# aspirin_carrier_board.net
KiCad netlist of a schematic drawn in EAGLE
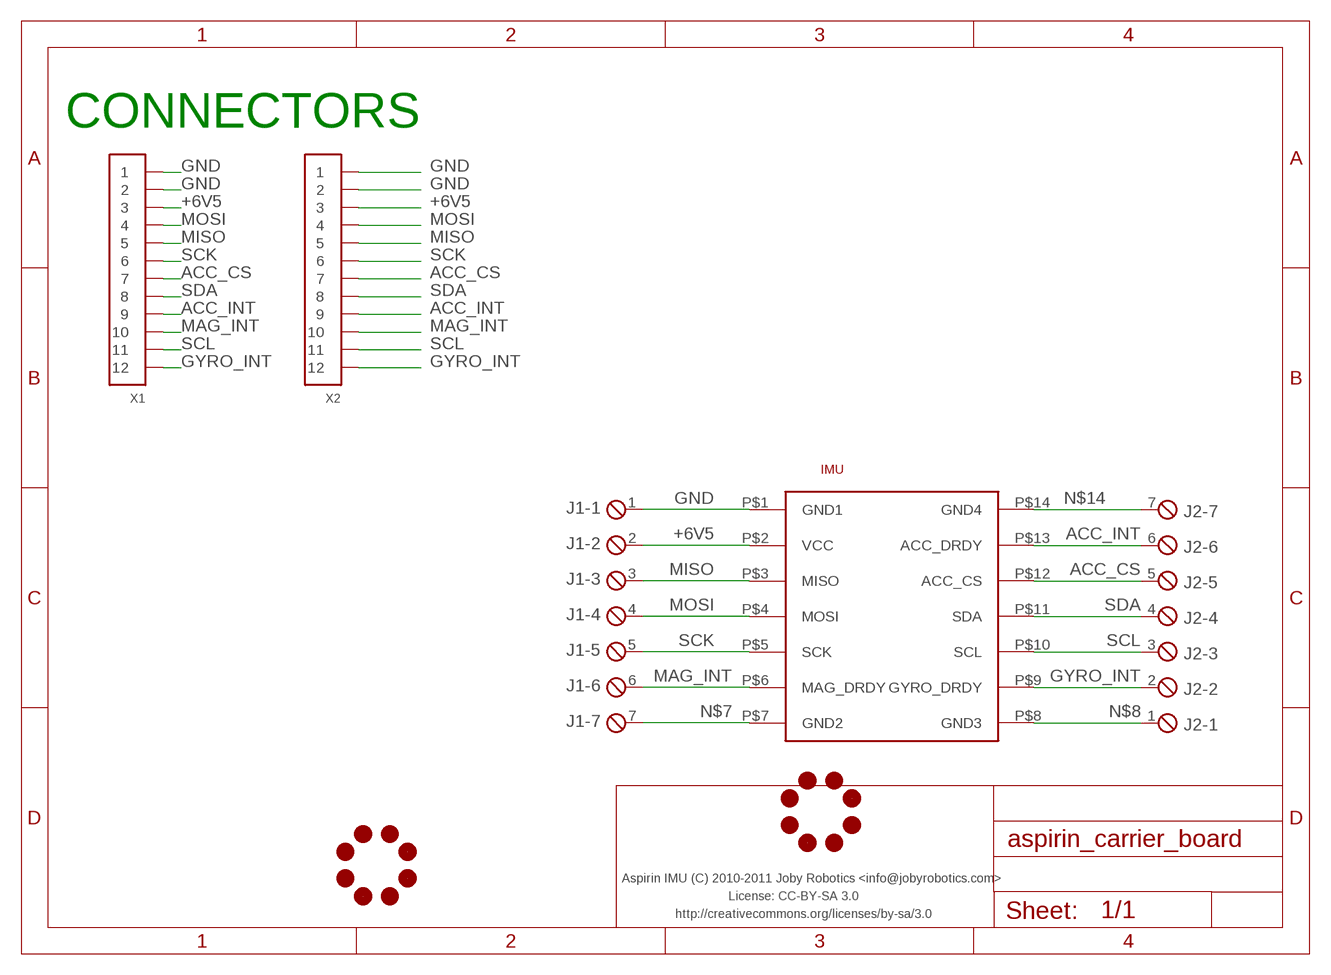
[diagram p0: schematic, sheet 1]

(export (version "E")
  (design (tool "Eeschema 10.0.6"))
  (components
    (comp (ref "IMU")
      (value "ASPIRIN")
      (footprint "eagle-import:ASPIRIN_1")
      (libsource (lib "eagle-import") (part "ASPIRIN"))
    )
    (comp (ref "J1")
      (value "MPT7")
      (footprint "eagle-import:7POL254")
      (libsource (lib "eagle-import") (part "MPT7"))
    )
    (comp (ref "J2")
      (value "MPT7")
      (footprint "eagle-import:7POL254")
      (libsource (lib "eagle-import") (part "MPT7"))
    )
    (comp (ref "JL1")
      (value "JOBY_LOGO-6MIL")
      (footprint "eagle-import:JOBY_LOGO_6MIL")
      (libsource (lib "eagle-import") (part "JOBY_LOGO-6MIL"))
    )
    (comp (ref "JL2")
      (value "JOBY_LOGO-6MIL")
      (footprint "eagle-import:JOBY_LOGO_6MIL")
      (libsource (lib "eagle-import") (part "JOBY_LOGO-6MIL"))
    )
    (comp (ref "X1")
      (value "CONN_12-1-53047")
      (footprint "eagle-import:PB-53047-12")
      (libsource (lib "eagle-import") (part "CONN_12-1-53047"))
    )
    (comp (ref "X2")
      (value "CONN_12-1-53261")
      (footprint "eagle-import:PB-53261-12")
      (libsource (lib "eagle-import") (part "CONN_12-1-53261"))
    )
  )
  (nets
    (net (code "1") (name "/+6V5") (class "Default")
      (node (ref "IMU") (pin "P$2") (pinfunction "VCC_P$2") (pintype "bidirectional"))
      (node (ref "J1") (pin "2") (pinfunction "1_2") (pintype "passive"))
      (node (ref "X1") (pin "3") (pinfunction "3_3") (pintype "bidirectional"))
      (node (ref "X2") (pin "3") (pinfunction "3_3") (pintype "bidirectional"))
    )
    (net (code "2") (name "/ACC_CS") (class "Default")
      (node (ref "IMU") (pin "P$12") (pinfunction "ACC_CS_P$12") (pintype "bidirectional"))
      (node (ref "J2") (pin "5") (pinfunction "1_5") (pintype "passive"))
      (node (ref "X1") (pin "7") (pinfunction "7_7") (pintype "bidirectional"))
      (node (ref "X2") (pin "7") (pinfunction "7_7") (pintype "bidirectional"))
    )
    (net (code "3") (name "/ACC_INT") (class "Default")
      (node (ref "IMU") (pin "P$13") (pinfunction "ACC_DRDY_P$13") (pintype "bidirectional"))
      (node (ref "J2") (pin "6") (pinfunction "1_6") (pintype "passive"))
      (node (ref "X1") (pin "9") (pinfunction "9_9") (pintype "bidirectional"))
      (node (ref "X2") (pin "9") (pinfunction "9_9") (pintype "bidirectional"))
    )
    (net (code "4") (name "/GND") (class "Default")
      (node (ref "IMU") (pin "P$1") (pinfunction "GND1_P$1") (pintype "bidirectional"))
      (node (ref "J1") (pin "1") (pinfunction "1_1") (pintype "passive"))
      (node (ref "X1") (pin "1") (pinfunction "1_1") (pintype "bidirectional"))
      (node (ref "X1") (pin "2") (pinfunction "2_2") (pintype "bidirectional"))
      (node (ref "X2") (pin "1") (pinfunction "1_1") (pintype "bidirectional"))
      (node (ref "X2") (pin "2") (pinfunction "2_2") (pintype "bidirectional"))
    )
    (net (code "5") (name "/GYRO_INT") (class "Default")
      (node (ref "IMU") (pin "P$9") (pinfunction "GYRO_DRDY_P$9") (pintype "bidirectional"))
      (node (ref "J2") (pin "2") (pinfunction "1_2") (pintype "passive"))
      (node (ref "X1") (pin "12") (pinfunction "12_12") (pintype "bidirectional"))
      (node (ref "X2") (pin "12") (pinfunction "12_12") (pintype "bidirectional"))
    )
    (net (code "6") (name "/MAG_INT") (class "Default")
      (node (ref "IMU") (pin "P$6") (pinfunction "MAG_DRDY_P$6") (pintype "bidirectional"))
      (node (ref "J1") (pin "6") (pinfunction "1_6") (pintype "passive"))
      (node (ref "X1") (pin "10") (pinfunction "10_10") (pintype "bidirectional"))
      (node (ref "X2") (pin "10") (pinfunction "10_10") (pintype "bidirectional"))
    )
    (net (code "7") (name "/MISO") (class "Default")
      (node (ref "IMU") (pin "P$3") (pinfunction "MISO_P$3") (pintype "bidirectional"))
      (node (ref "J1") (pin "3") (pinfunction "1_3") (pintype "passive"))
      (node (ref "X1") (pin "5") (pinfunction "5_5") (pintype "bidirectional"))
      (node (ref "X2") (pin "5") (pinfunction "5_5") (pintype "bidirectional"))
    )
    (net (code "8") (name "/MOSI") (class "Default")
      (node (ref "IMU") (pin "P$4") (pinfunction "MOSI_P$4") (pintype "bidirectional"))
      (node (ref "J1") (pin "4") (pinfunction "1_4") (pintype "passive"))
      (node (ref "X1") (pin "4") (pinfunction "4_4") (pintype "bidirectional"))
      (node (ref "X2") (pin "4") (pinfunction "4_4") (pintype "bidirectional"))
    )
    (net (code "9") (name "/N$7") (class "Default")
      (node (ref "IMU") (pin "P$7") (pinfunction "GND2_P$7") (pintype "bidirectional"))
      (node (ref "J1") (pin "7") (pinfunction "1_7") (pintype "passive"))
    )
    (net (code "10") (name "/N$8") (class "Default")
      (node (ref "IMU") (pin "P$8") (pinfunction "GND3_P$8") (pintype "bidirectional"))
      (node (ref "J2") (pin "1") (pinfunction "1_1") (pintype "passive"))
    )
    (net (code "11") (name "/N$14") (class "Default")
      (node (ref "IMU") (pin "P$14") (pinfunction "GND4_P$14") (pintype "bidirectional"))
      (node (ref "J2") (pin "7") (pinfunction "1_7") (pintype "passive"))
    )
    (net (code "12") (name "/SCK") (class "Default")
      (node (ref "IMU") (pin "P$5") (pinfunction "SCK_P$5") (pintype "bidirectional"))
      (node (ref "J1") (pin "5") (pinfunction "1_5") (pintype "passive"))
      (node (ref "X1") (pin "6") (pinfunction "6_6") (pintype "bidirectional"))
      (node (ref "X2") (pin "6") (pinfunction "6_6") (pintype "bidirectional"))
    )
    (net (code "13") (name "/SCL") (class "Default")
      (node (ref "IMU") (pin "P$10") (pinfunction "SCL_P$10") (pintype "bidirectional"))
      (node (ref "J2") (pin "3") (pinfunction "1_3") (pintype "passive"))
      (node (ref "X1") (pin "11") (pinfunction "11_11") (pintype "bidirectional"))
      (node (ref "X2") (pin "11") (pinfunction "11_11") (pintype "bidirectional"))
    )
    (net (code "14") (name "/SDA") (class "Default")
      (node (ref "IMU") (pin "P$11") (pinfunction "SDA_P$11") (pintype "bidirectional"))
      (node (ref "J2") (pin "4") (pinfunction "1_4") (pintype "passive"))
      (node (ref "X1") (pin "8") (pinfunction "8_8") (pintype "bidirectional"))
      (node (ref "X2") (pin "8") (pinfunction "8_8") (pintype "bidirectional"))
    )
  )
)
